# RJ-45_Sensor_Breakout_Logo_2_Fin.net
KiCad netlist of a schematic drawn in EAGLE
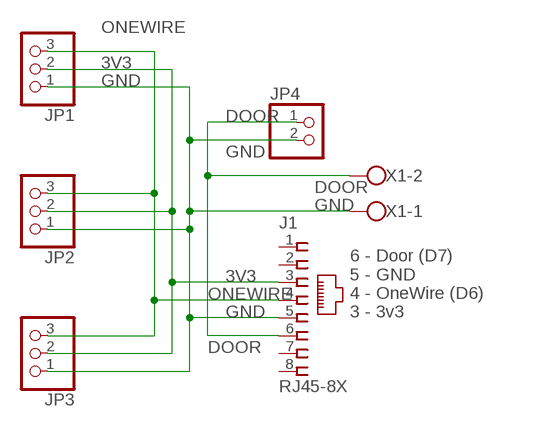
[diagram p0: schematic, sheet 1]

(export (version "E")
  (design (tool "Eeschema 10.0.6"))
  (components
    (comp (ref "J1")
      (value "RJ45-8X")
      (footprint "eagle-import:RJ45-NO-SHIELD-NOLINE")
      (libsource (lib "eagle-import") (part "RJ45-8X"))
    )
    (comp (ref "JP1")
      (value "PINHD-1X3")
      (footprint "eagle-import:1X03")
      (libsource (lib "eagle-import") (part "PINHD-1X3"))
    )
    (comp (ref "JP2")
      (value "PINHD-1X3")
      (footprint "eagle-import:1X03")
      (libsource (lib "eagle-import") (part "PINHD-1X3"))
    )
    (comp (ref "JP3")
      (value "PINHD-1X3")
      (footprint "eagle-import:1X03")
      (libsource (lib "eagle-import") (part "PINHD-1X3"))
    )
    (comp (ref "JP4")
      (value "PINHD-1X2")
      (footprint "eagle-import:1X02")
      (libsource (lib "eagle-import") (part "PINHD-1X2"))
    )
    (comp (ref "X1")
      (value "W237-102")
      (footprint "eagle-import:W237-102")
      (fields (field (name "MPN") "237-102"))
      (libsource (lib "eagle-import") (part "W237-102"))
    )
  )
  (nets
    (net (code "1") (name "/3V3") (class "Default")
      (node (ref "J1") (pin "3") (pinfunction "3_3") (pintype "passive"))
      (node (ref "JP1") (pin "2") (pinfunction "2_2") (pintype "passive"))
      (node (ref "JP2") (pin "2") (pinfunction "2_2") (pintype "passive"))
      (node (ref "JP3") (pin "2") (pinfunction "2_2") (pintype "passive"))
    )
    (net (code "2") (name "/DOOR") (class "Default")
      (node (ref "J1") (pin "6") (pinfunction "6_6") (pintype "passive"))
      (node (ref "JP4") (pin "1") (pinfunction "1_1") (pintype "passive"))
      (node (ref "X1") (pin "2") (pinfunction "KL_2") (pintype "passive"))
    )
    (net (code "3") (name "/GND") (class "Default")
      (node (ref "J1") (pin "5") (pinfunction "5_5") (pintype "passive"))
      (node (ref "JP1") (pin "1") (pinfunction "1_1") (pintype "passive"))
      (node (ref "JP2") (pin "1") (pinfunction "1_1") (pintype "passive"))
      (node (ref "JP3") (pin "1") (pinfunction "1_1") (pintype "passive"))
      (node (ref "JP4") (pin "2") (pinfunction "2_2") (pintype "passive"))
      (node (ref "X1") (pin "1") (pinfunction "KL_1") (pintype "passive"))
    )
    (net (code "4") (name "/ONEWIRE") (class "Default")
      (node (ref "J1") (pin "4") (pinfunction "4_4") (pintype "passive"))
      (node (ref "JP1") (pin "3") (pinfunction "3_3") (pintype "passive"))
      (node (ref "JP2") (pin "3") (pinfunction "3_3") (pintype "passive"))
      (node (ref "JP3") (pin "3") (pinfunction "3_3") (pintype "passive"))
    )
    (net (code "5") (name "unconnected-(J1-Pad1)") (class "Default")
      (node (ref "J1") (pin "1") (pinfunction "1_1") (pintype "passive"))
    )
    (net (code "6") (name "unconnected-(J1-Pad2)") (class "Default")
      (node (ref "J1") (pin "2") (pinfunction "2_2") (pintype "passive"))
    )
    (net (code "7") (name "unconnected-(J1-Pad7)") (class "Default")
      (node (ref "J1") (pin "7") (pinfunction "7_7") (pintype "passive"))
    )
    (net (code "8") (name "unconnected-(J1-Pad8)") (class "Default")
      (node (ref "J1") (pin "8") (pinfunction "8_8") (pintype "passive"))
    )
  )
)
